# IntegratedConnectors.net
KiCad netlist of a schematic drawn in Altium Designer
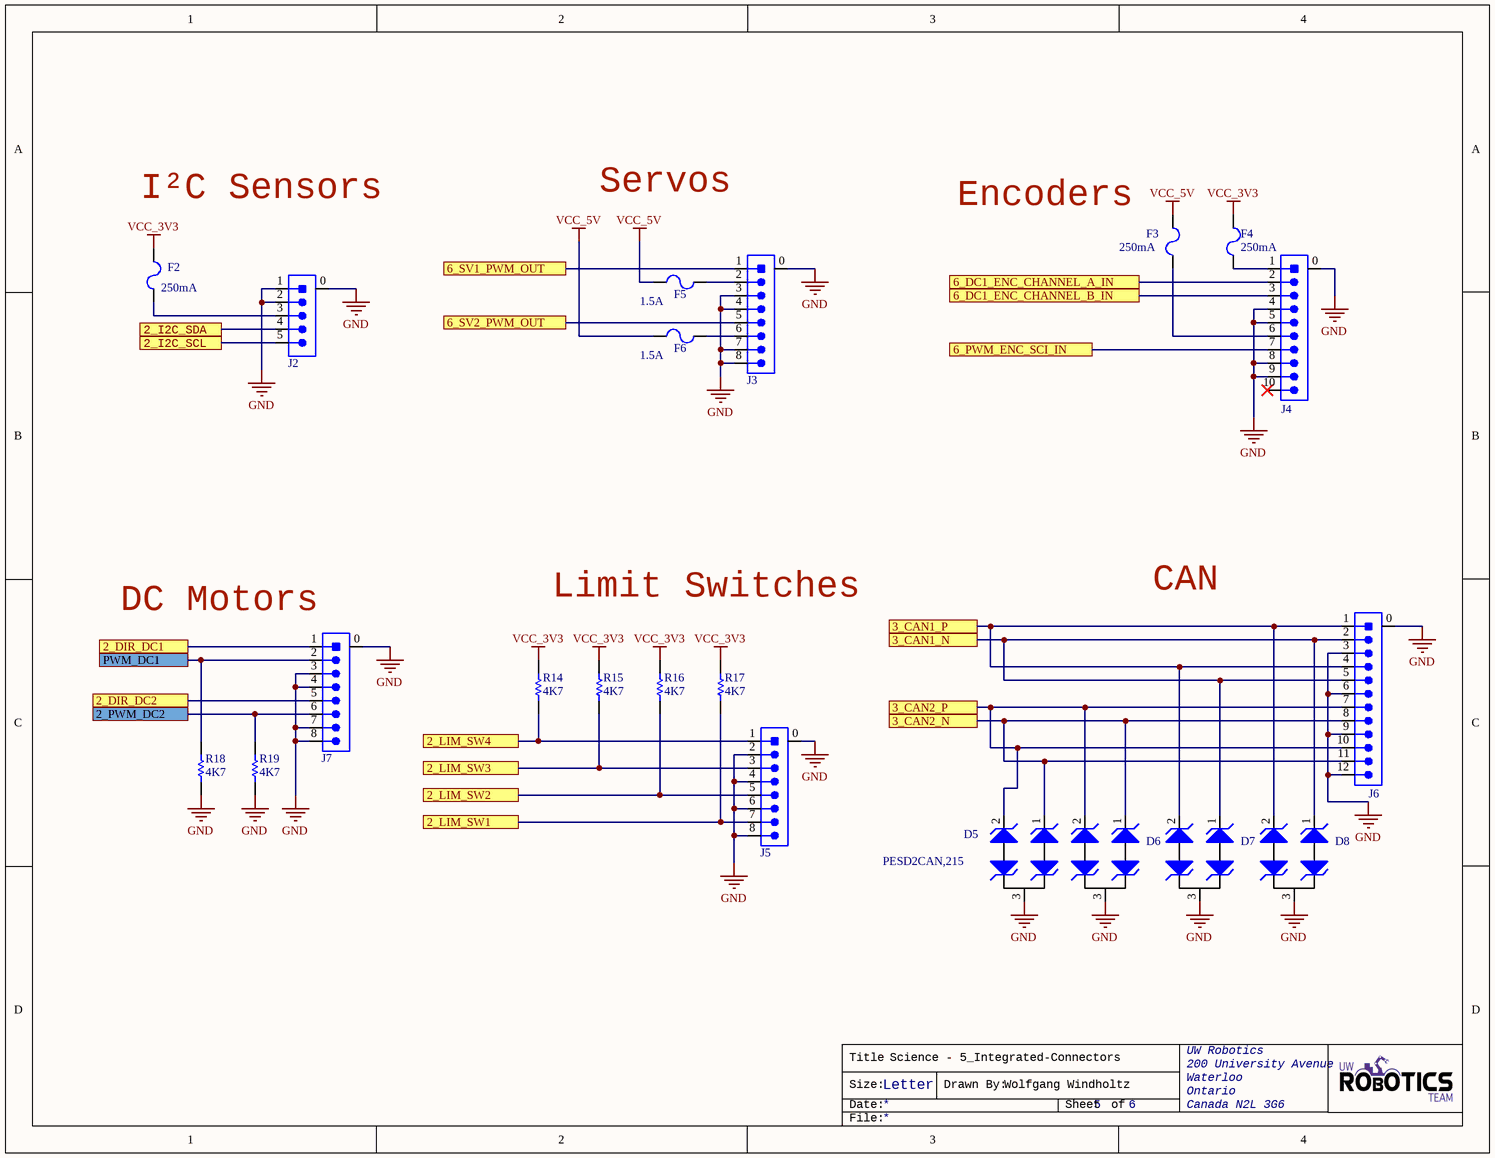
[diagram p0: IntegratedConnectors.SchDoc]

(export (version "E")
  (design (tool "Eeschema 10.0.6"))
  (components
    (comp (ref "D5")
      (value "TVS_DIODE_CAN")
      (footprint "TVS_DIODE_CAN")
      (description "TVS DIODE 24V 41V SOT323-3")
      (fields
        (field (name "MANUFACTURER") "Nexperia USA Inc.")
        (field (name "MANUFACTURER PART NUMBER") "PESD2CAN,215")
      )
      (libsource (lib "UWRT_Schematic_Library_2020") (part "TVS_DIODE_CAN"))
    )
    (comp (ref "D6")
      (value "TVS_DIODE_CAN")
      (footprint "TVS_DIODE_CAN")
      (description "TVS DIODE 24V 41V SOT323-3")
      (fields (field (name "MANUFACTURER") "Nexperia USA Inc."))
      (libsource (lib "UWRT_Schematic_Library_2020") (part "TVS_DIODE_CAN"))
    )
    (comp (ref "D7")
      (value "TVS_DIODE_CAN")
      (footprint "TVS_DIODE_CAN")
      (description "TVS DIODE 24V 41V SOT323-3")
      (fields (field (name "MANUFACTURER") "Nexperia USA Inc."))
      (libsource (lib "UWRT_Schematic_Library_2020") (part "TVS_DIODE_CAN"))
    )
    (comp (ref "D8")
      (value "TVS_DIODE_CAN")
      (footprint "TVS_DIODE_CAN")
      (description "TVS DIODE 24V 41V SOT323-3")
      (fields (field (name "MANUFACTURER") "Nexperia USA Inc."))
      (libsource (lib "UWRT_Schematic_Library_2020") (part "TVS_DIODE_CAN"))
    )
    (comp (ref "F2")
      (value "FUSE_250mA_0603")
      (footprint "FUSE_0603")
      (description "FUSE SMD 250mA 32V")
      (fields (field (name "CURRENT RATING") "250mA"))
      (libsource (lib "UWRT_Schematic_Library_2020") (part "FUSE_250mA_0603"))
    )
    (comp (ref "F3")
      (value "FUSE_250mA_0603")
      (footprint "FUSE_0603")
      (description "FUSE SMD 250mA 32V")
      (fields (field (name "CURRENT RATING") "250mA"))
      (libsource (lib "UWRT_Schematic_Library_2020") (part "FUSE_250mA_0603"))
    )
    (comp (ref "F4")
      (value "FUSE_250mA_0603")
      (footprint "FUSE_0603")
      (description "FUSE SMD 250mA 32V")
      (fields (field (name "CURRENT RATING") "250mA"))
      (libsource (lib "UWRT_Schematic_Library_2020") (part "FUSE_250mA_0603"))
    )
    (comp (ref "F5")
      (value "FUSE_1.5A_0603")
      (footprint "FUSE_0603")
      (description "FUSE SMD 1.5A 32V")
      (fields (field (name "CURRENT RATING") "1.5A"))
      (libsource (lib "UWRT_Schematic_Library_2020") (part "FUSE_1.5A_0603"))
    )
    (comp (ref "F6")
      (value "FUSE_1.5A_0603")
      (footprint "FUSE_0603")
      (description "FUSE SMD 1.5A 32V")
      (fields (field (name "CURRENT RATING") "1.5A"))
      (libsource (lib "UWRT_Schematic_Library_2020") (part "FUSE_1.5A_0603"))
    )
    (comp (ref "J2")
      (value "CON_5M_SM_VERT")
      (footprint "MOLEX-5025840570")
      (description "CONN HEADER SMD VERTICAL 1.5MM PITCH")
      (libsource (lib "UWRT_Schematic_Library_2020") (part "CON_5M_SM_VERT"))
    )
    (comp (ref "J3")
      (value "CON_8M_SM_RA")
      (footprint "MOLEX-5025850870")
      (description "CONN HEADER SMD RIGHT ANGLE 1.5 MM PITCH")
      (fields (field (name "MANUFACTURER") "Molex") (field (name "MANUFACTURER PART NUMBER") "5025850870"))
      (libsource (lib "UWRT_Schematic_Library_2020") (part "CON_8M_SM_RA"))
    )
    (comp (ref "J4")
      (value "~")
      (footprint "MOLEX-5025851070")
      (description "CONN HEADER SMD RIGHT ANGLE 1.5 MM PITCH")
      (libsource (lib "UWRT_Schematic_Library_2020") (part "CON_10M_SM_RA"))
    )
    (comp (ref "J5")
      (value "CON_8M_SM_RA")
      (footprint "MOLEX-5025850870")
      (description "CONN HEADER SMD RIGHT ANGLE 1.5 MM PITCH")
      (fields (field (name "MANUFACTURER") "Molex") (field (name "MANUFACTURER PART NUMBER") "5025850870"))
      (libsource (lib "UWRT_Schematic_Library_2020") (part "CON_8M_SM_RA"))
    )
    (comp (ref "J6")
      (value "~")
      (footprint "MOLEX-5025851270")
      (description "CONN HEADER SMD RIGHT ANGLE 1.5MM PITCH")
      (libsource (lib "UWRT_Schematic_Library_2020") (part "CON_12M_SM_RA"))
    )
    (comp (ref "J7")
      (value "CON_8M_SM_RA")
      (footprint "MOLEX-5025850870")
      (description "CONN HEADER SMD RIGHT ANGLE 1.5 MM PITCH")
      (fields (field (name "MANUFACTURER") "Molex") (field (name "MANUFACTURER PART NUMBER") "5025850870"))
      (libsource (lib "UWRT_Schematic_Library_2020") (part "CON_8M_SM_RA"))
    )
    (comp (ref "R14")
      (value "4K7")
      (footprint "RESC0603(1608)_N")
      (description "RES SMD 4.7K OHM 5% 1/10W 0603")
      (fields (field (name "MANUFACTURER") "Yageo") (field (name "MPN") "RC0603JR-074K7L"))
      (libsource (lib "UWRT_Schematic_Library_2020") (part "RES_4K7_0603"))
    )
    (comp (ref "R15")
      (value "4K7")
      (footprint "RESC0603(1608)_N")
      (description "RES SMD 4.7K OHM 5% 1/10W 0603")
      (fields (field (name "MANUFACTURER") "Yageo") (field (name "MPN") "RC0603JR-074K7L"))
      (libsource (lib "UWRT_Schematic_Library_2020") (part "RES_4K7_0603"))
    )
    (comp (ref "R16")
      (value "4K7")
      (footprint "RESC0603(1608)_N")
      (description "RES SMD 4.7K OHM 5% 1/10W 0603")
      (fields (field (name "MANUFACTURER") "Yageo") (field (name "MPN") "RC0603JR-074K7L"))
      (libsource (lib "UWRT_Schematic_Library_2020") (part "RES_4K7_0603"))
    )
    (comp (ref "R17")
      (value "4K7")
      (footprint "RESC0603(1608)_N")
      (description "RES SMD 4.7K OHM 5% 1/10W 0603")
      (fields (field (name "MANUFACTURER") "Yageo") (field (name "MPN") "RC0603JR-074K7L"))
      (libsource (lib "UWRT_Schematic_Library_2020") (part "RES_4K7_0603"))
    )
    (comp (ref "R18")
      (value "4K7")
      (footprint "RESC0603(1608)_N")
      (description "RES SMD 4.7K OHM 5% 1/10W 0603")
      (fields (field (name "MANUFACTURER") "Yageo") (field (name "MPN") "RC0603JR-074K7L"))
      (libsource (lib "UWRT_Schematic_Library_2020") (part "RES_4K7_0603"))
    )
    (comp (ref "R19")
      (value "4K7")
      (footprint "RESC0603(1608)_N")
      (description "RES SMD 4.7K OHM 5% 1/10W 0603")
      (fields (field (name "MANUFACTURER") "Yageo") (field (name "MPN") "RC0603JR-074K7L"))
      (libsource (lib "UWRT_Schematic_Library_2020") (part "RES_4K7_0603"))
    )
  )
  (nets
    (net (code "1") (name "/2_DIR_DC1") (class "Default")
      (node (ref "J7") (pin "1") (pinfunction "1_1") (pintype "passive"))
    )
    (net (code "2") (name "/2_DIR_DC2") (class "Default")
      (node (ref "J7") (pin "5") (pinfunction "5_5") (pintype "passive"))
    )
    (net (code "3") (name "/2_I2C_SCL") (class "Default")
      (node (ref "J2") (pin "5") (pinfunction "5_5") (pintype "passive"))
    )
    (net (code "4") (name "/2_I2C_SDA") (class "Default")
      (node (ref "J2") (pin "4") (pinfunction "4_4") (pintype "passive"))
    )
    (net (code "5") (name "/2_LIM_SW1") (class "Default")
      (node (ref "J5") (pin "7") (pinfunction "6_7") (pintype "passive"))
      (node (ref "R17") (pin "1") (pinfunction "1_1") (pintype "passive"))
    )
    (net (code "6") (name "/2_LIM_SW2") (class "Default")
      (node (ref "J5") (pin "5") (pinfunction "5_5") (pintype "passive"))
      (node (ref "R16") (pin "1") (pinfunction "1_1") (pintype "passive"))
    )
    (net (code "7") (name "/2_LIM_SW3") (class "Default")
      (node (ref "J5") (pin "3") (pinfunction "3_3") (pintype "passive"))
      (node (ref "R15") (pin "1") (pinfunction "1_1") (pintype "passive"))
    )
    (net (code "8") (name "/2_LIM_SW4") (class "Default")
      (node (ref "J5") (pin "1") (pinfunction "1_1") (pintype "passive"))
      (node (ref "R14") (pin "1") (pinfunction "1_1") (pintype "passive"))
    )
    (net (code "9") (name "/2_PWM_DC2") (class "Default")
      (node (ref "J7") (pin "6") (pinfunction "6_6") (pintype "passive"))
      (node (ref "R19") (pin "1") (pinfunction "1_1") (pintype "passive"))
    )
    (net (code "10") (name "/3_CAN1_N") (class "Default")
      (node (ref "D7") (pin "1") (pinfunction "1_1") (pintype "passive"))
      (node (ref "D8") (pin "1") (pinfunction "1_1") (pintype "passive"))
      (node (ref "J6") (pin "2") (pinfunction "2_2") (pintype "passive"))
      (node (ref "J6") (pin "5") (pinfunction "5_5") (pintype "passive"))
    )
    (net (code "11") (name "/3_CAN1_P") (class "Default")
      (node (ref "D7") (pin "2") (pinfunction "2_2") (pintype "passive"))
      (node (ref "D8") (pin "2") (pinfunction "2_2") (pintype "passive"))
      (node (ref "J6") (pin "1") (pinfunction "1_1") (pintype "passive"))
      (node (ref "J6") (pin "4") (pinfunction "4_4") (pintype "passive"))
    )
    (net (code "12") (name "/3_CAN2_N") (class "Default")
      (node (ref "D5") (pin "1") (pinfunction "1_1") (pintype "passive"))
      (node (ref "D6") (pin "1") (pinfunction "1_1") (pintype "passive"))
      (node (ref "J6") (pin "11") (pinfunction "11_11") (pintype "passive"))
      (node (ref "J6") (pin "8") (pinfunction "6_8") (pintype "passive"))
    )
    (net (code "13") (name "/3_CAN2_P") (class "Default")
      (node (ref "D5") (pin "2") (pinfunction "2_2") (pintype "passive"))
      (node (ref "D6") (pin "2") (pinfunction "2_2") (pintype "passive"))
      (node (ref "J6") (pin "10") (pinfunction "10_10") (pintype "passive"))
      (node (ref "J6") (pin "7") (pinfunction "6_7") (pintype "passive"))
    )
    (net (code "14") (name "/6_DC1_ENC_CHANNEL_A_IN") (class "Default")
      (node (ref "J4") (pin "2") (pinfunction "2_2") (pintype "passive"))
    )
    (net (code "15") (name "/6_DC1_ENC_CHANNEL_B_IN") (class "Default")
      (node (ref "J4") (pin "3") (pinfunction "3_3") (pintype "passive"))
    )
    (net (code "16") (name "/6_PWM_ENC_SCI_IN") (class "Default")
      (node (ref "J4") (pin "7") (pinfunction "6_7") (pintype "passive"))
    )
    (net (code "17") (name "/6_SV1_PWM_OUT") (class "Default")
      (node (ref "J3") (pin "1") (pinfunction "1_1") (pintype "passive"))
    )
    (net (code "18") (name "/6_SV2_PWM_OUT") (class "Default")
      (node (ref "J3") (pin "5") (pinfunction "5_5") (pintype "passive"))
    )
    (net (code "19") (name "/PWM_DC1") (class "Default")
      (node (ref "J7") (pin "2") (pinfunction "2_2") (pintype "passive"))
      (node (ref "R18") (pin "1") (pinfunction "1_1") (pintype "passive"))
    )
    (net (code "20") (name "GND") (class "Default")
      (node (ref "D5") (pin "3") (pinfunction "3_3") (pintype "passive"))
      (node (ref "D6") (pin "3") (pinfunction "3_3") (pintype "passive"))
      (node (ref "D7") (pin "3") (pinfunction "3_3") (pintype "passive"))
      (node (ref "D8") (pin "3") (pinfunction "3_3") (pintype "passive"))
      (node (ref "J2") (pin "0") (pinfunction "0_0") (pintype "passive"))
      (node (ref "J2") (pin "1") (pinfunction "1_1") (pintype "passive"))
      (node (ref "J2") (pin "2") (pinfunction "2_2") (pintype "passive"))
      (node (ref "J3") (pin "0") (pinfunction "0_0") (pintype "passive"))
      (node (ref "J3") (pin "3") (pinfunction "3_3") (pintype "passive"))
      (node (ref "J3") (pin "4") (pinfunction "4_4") (pintype "passive"))
      (node (ref "J3") (pin "7") (pinfunction "6_7") (pintype "passive"))
      (node (ref "J3") (pin "8") (pinfunction "6_8") (pintype "passive"))
      (node (ref "J4") (pin "0") (pinfunction "0_0") (pintype "passive"))
      (node (ref "J4") (pin "4") (pinfunction "4_4") (pintype "passive"))
      (node (ref "J4") (pin "5") (pinfunction "5_5") (pintype "passive"))
      (node (ref "J4") (pin "8") (pinfunction "6_8") (pintype "passive"))
      (node (ref "J4") (pin "9") (pinfunction "9_9") (pintype "passive"))
      (node (ref "J5") (pin "0") (pinfunction "0_0") (pintype "passive"))
      (node (ref "J5") (pin "2") (pinfunction "2_2") (pintype "passive"))
      (node (ref "J5") (pin "4") (pinfunction "4_4") (pintype "passive"))
      (node (ref "J5") (pin "6") (pinfunction "6_6") (pintype "passive"))
      (node (ref "J5") (pin "8") (pinfunction "6_8") (pintype "passive"))
      (node (ref "J6") (pin "0") (pinfunction "0_0") (pintype "passive"))
      (node (ref "J6") (pin "12") (pinfunction "12_12") (pintype "passive"))
      (node (ref "J6") (pin "3") (pinfunction "3_3") (pintype "passive"))
      (node (ref "J6") (pin "6") (pinfunction "6_6") (pintype "passive"))
      (node (ref "J6") (pin "9") (pinfunction "9_9") (pintype "passive"))
      (node (ref "J7") (pin "0") (pinfunction "0_0") (pintype "passive"))
      (node (ref "J7") (pin "3") (pinfunction "3_3") (pintype "passive"))
      (node (ref "J7") (pin "4") (pinfunction "4_4") (pintype "passive"))
      (node (ref "J7") (pin "7") (pinfunction "6_7") (pintype "passive"))
      (node (ref "J7") (pin "8") (pinfunction "6_8") (pintype "passive"))
      (node (ref "R18") (pin "2") (pinfunction "2_2") (pintype "passive"))
      (node (ref "R19") (pin "2") (pinfunction "2_2") (pintype "passive"))
    )
    (net (code "21") (name "Net-(F2-Pad2)") (class "Default")
      (node (ref "F2") (pin "2") (pinfunction "2_2") (pintype "passive"))
      (node (ref "J2") (pin "3") (pinfunction "3_3") (pintype "passive"))
    )
    (net (code "22") (name "Net-(F3-Pad1)") (class "Default")
      (node (ref "F3") (pin "1") (pinfunction "1_1") (pintype "passive"))
      (node (ref "J4") (pin "6") (pinfunction "6_6") (pintype "passive"))
    )
    (net (code "23") (name "Net-(F4-Pad1)") (class "Default")
      (node (ref "F4") (pin "1") (pinfunction "1_1") (pintype "passive"))
      (node (ref "J4") (pin "1") (pinfunction "1_1") (pintype "passive"))
    )
    (net (code "24") (name "Net-(F5-Pad1)") (class "Default")
      (node (ref "F5") (pin "1") (pinfunction "1_1") (pintype "passive"))
      (node (ref "J3") (pin "2") (pinfunction "2_2") (pintype "passive"))
    )
    (net (code "25") (name "Net-(F6-Pad1)") (class "Default")
      (node (ref "F6") (pin "1") (pinfunction "1_1") (pintype "passive"))
      (node (ref "J3") (pin "6") (pinfunction "6_6") (pintype "passive"))
    )
    (net (code "26") (name "VCC_3V3") (class "Default")
      (node (ref "F2") (pin "1") (pinfunction "1_1") (pintype "passive"))
      (node (ref "F4") (pin "2") (pinfunction "2_2") (pintype "passive"))
      (node (ref "R14") (pin "2") (pinfunction "2_2") (pintype "passive"))
      (node (ref "R15") (pin "2") (pinfunction "2_2") (pintype "passive"))
      (node (ref "R16") (pin "2") (pinfunction "2_2") (pintype "passive"))
      (node (ref "R17") (pin "2") (pinfunction "2_2") (pintype "passive"))
    )
    (net (code "27") (name "VCC_5V") (class "Default")
      (node (ref "F3") (pin "2") (pinfunction "2_2") (pintype "passive"))
      (node (ref "F5") (pin "2") (pinfunction "2_2") (pintype "passive"))
      (node (ref "F6") (pin "2") (pinfunction "2_2") (pintype "passive"))
    )
    (net (code "28") (name "unconnected-(J4-Pad10)") (class "Default")
      (node (ref "J4") (pin "10") (pinfunction "10_10") (pintype "passive+no_connect"))
    )
  )
)
